# dueSkelMADE.net
KiCad netlist of a schematic drawn in EAGLE
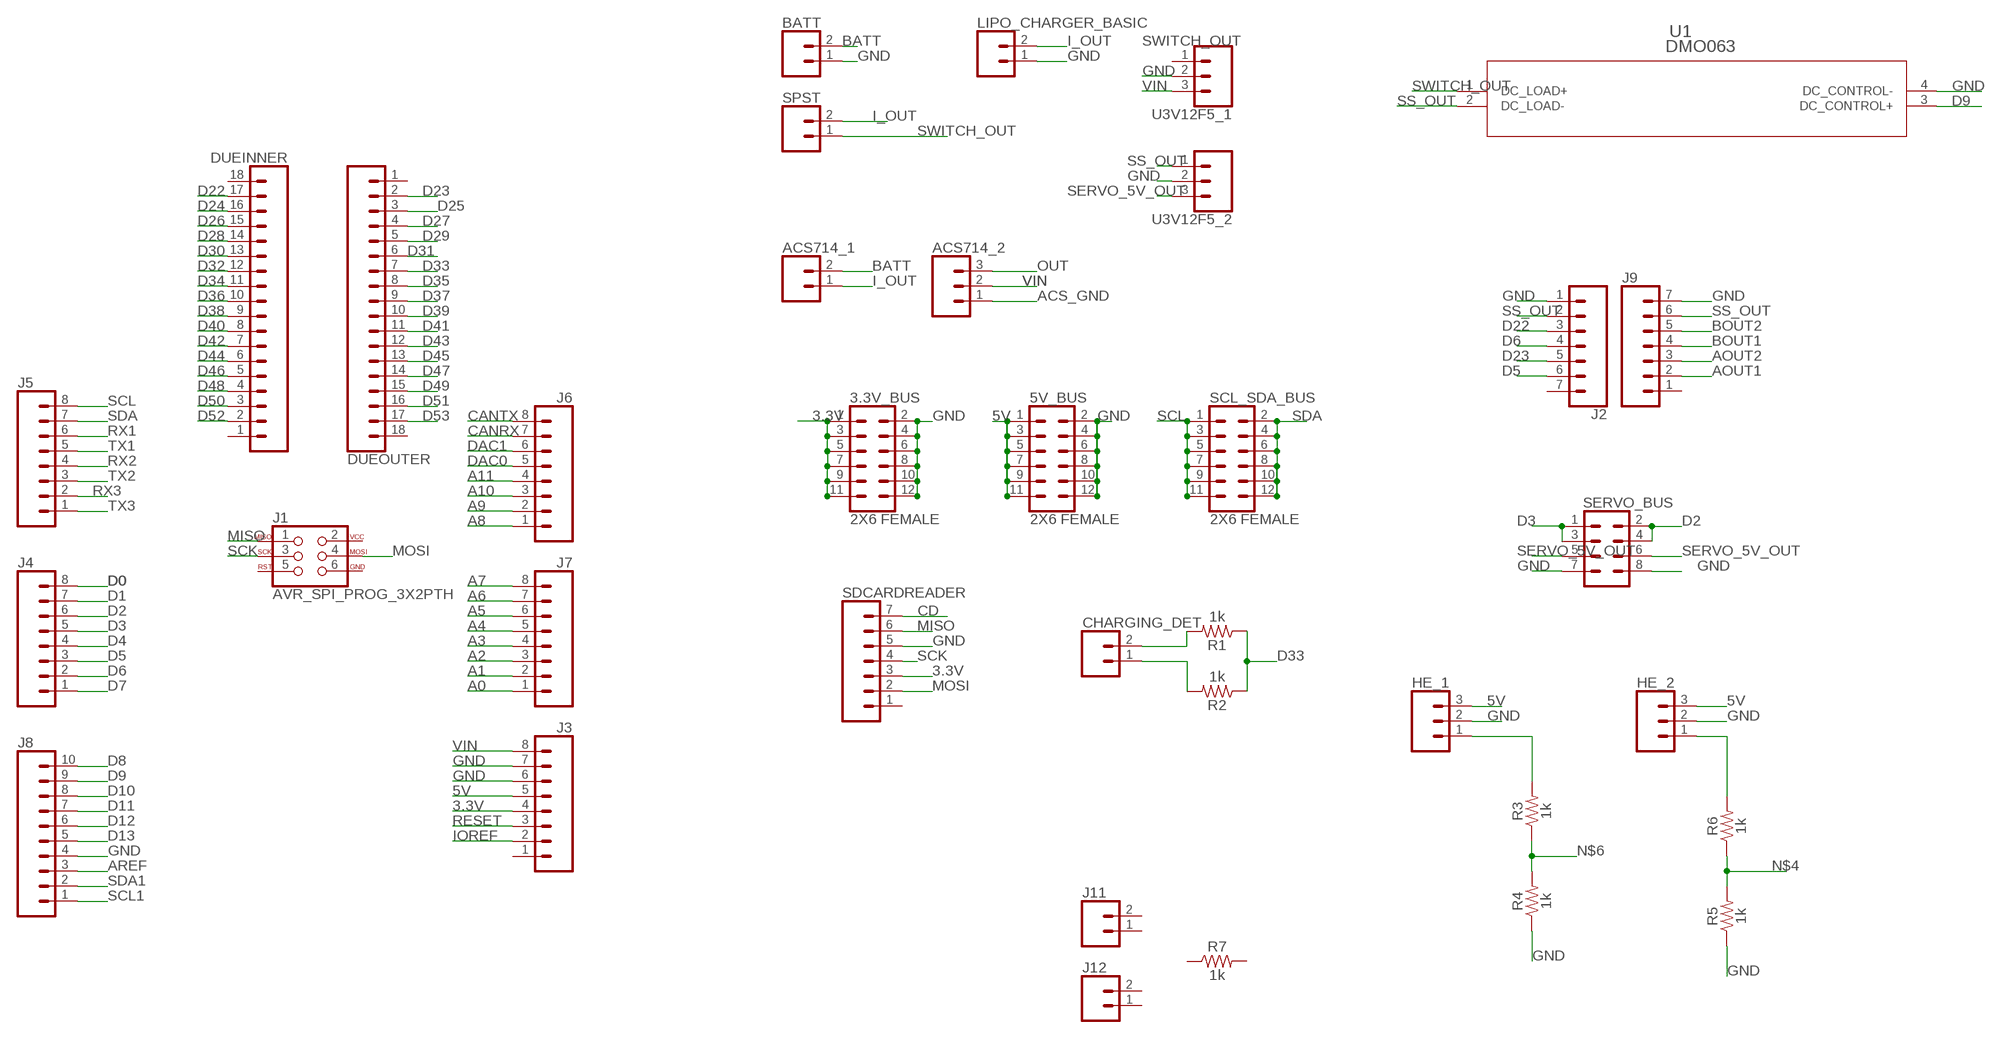
[diagram p0: schematic, sheet 1]

(export (version "E")
  (design (tool "Eeschema 10.0.6"))
  (components
    (comp (ref "3.3V_BUS")
      (value "2X6 FEMALE")
      (footprint "eagle-import:2X6")
      (libsource (lib "eagle-import") (part "CONN_06X2PTH_FEMALE"))
    )
    (comp (ref "5V_BUS")
      (value "2X6 FEMALE")
      (footprint "eagle-import:2X6")
      (libsource (lib "eagle-import") (part "CONN_06X2PTH_FEMALE"))
    )
    (comp (ref "ACS714_1")
      (value "CONN_02")
      (footprint "eagle-import:1X02")
      (libsource (lib "eagle-import") (part "CONN_02"))
    )
    (comp (ref "ACS714_2")
      (value "CONN_03")
      (footprint "eagle-import:1X03")
      (libsource (lib "eagle-import") (part "CONN_03"))
    )
    (comp (ref "BATT")
      (value "CONN_02")
      (footprint "eagle-import:1X02")
      (libsource (lib "eagle-import") (part "CONN_02"))
    )
    (comp (ref "CHARGING_DET")
      (value "CONN_02")
      (footprint "eagle-import:1X02")
      (libsource (lib "eagle-import") (part "CONN_02"))
    )
    (comp (ref "DUEINNER")
      (value "CONN_18")
      (footprint "eagle-import:1X18")
      (libsource (lib "eagle-import") (part "CONN_18"))
    )
    (comp (ref "DUEOUTER")
      (value "CONN_18")
      (footprint "eagle-import:1X18")
      (libsource (lib "eagle-import") (part "CONN_18"))
    )
    (comp (ref "HE_1")
      (value "CONN_03")
      (footprint "eagle-import:1X03")
      (libsource (lib "eagle-import") (part "CONN_03"))
    )
    (comp (ref "HE_2")
      (value "CONN_03")
      (footprint "eagle-import:1X03")
      (libsource (lib "eagle-import") (part "CONN_03"))
    )
    (comp (ref "J1")
      (value "AVR_SPI_PROG_3X2PTH")
      (footprint "eagle-import:2X3")
      (libsource (lib "eagle-import") (part "AVR_SPI_PROG_3X2PTH"))
    )
    (comp (ref "J2")
      (value "CONN_07")
      (footprint "eagle-import:1X07")
      (libsource (lib "eagle-import") (part "CONN_07"))
    )
    (comp (ref "J3")
      (value "CONN_08\"")
      (footprint "eagle-import:1X08")
      (libsource (lib "eagle-import") (part "CONN_08{dblquote}"))
    )
    (comp (ref "J4")
      (value "CONN_08\"")
      (footprint "eagle-import:1X08")
      (libsource (lib "eagle-import") (part "CONN_08{dblquote}"))
    )
    (comp (ref "J5")
      (value "CONN_08\"")
      (footprint "eagle-import:1X08")
      (libsource (lib "eagle-import") (part "CONN_08{dblquote}"))
    )
    (comp (ref "J6")
      (value "CONN_08\"")
      (footprint "eagle-import:1X08")
      (libsource (lib "eagle-import") (part "CONN_08{dblquote}"))
    )
    (comp (ref "J7")
      (value "CONN_08\"")
      (footprint "eagle-import:1X08")
      (libsource (lib "eagle-import") (part "CONN_08{dblquote}"))
    )
    (comp (ref "J8")
      (value "CONN_10\"")
      (footprint "eagle-import:1X10")
      (libsource (lib "eagle-import") (part "CONN_10{dblquote}"))
    )
    (comp (ref "J9")
      (value "CONN_07")
      (footprint "eagle-import:1X07")
      (libsource (lib "eagle-import") (part "CONN_07"))
    )
    (comp (ref "J11")
      (value "CONN_02")
      (footprint "eagle-import:1X02")
      (libsource (lib "eagle-import") (part "CONN_02"))
    )
    (comp (ref "J12")
      (value "CONN_02")
      (footprint "eagle-import:1X02")
      (libsource (lib "eagle-import") (part "CONN_02"))
    )
    (comp (ref "LIPO_CHARGER_BASIC")
      (value "CONN_02")
      (footprint "eagle-import:1X02")
      (libsource (lib "eagle-import") (part "CONN_02"))
    )
    (comp (ref "R1")
      (value "1k")
      (footprint "eagle-import:AXIAL-0.3")
      (libsource (lib "eagle-import") (part "1KOHM-HORIZ-1/4W-1%"))
    )
    (comp (ref "R2")
      (value "1k")
      (footprint "eagle-import:AXIAL-0.3")
      (libsource (lib "eagle-import") (part "1KOHM-HORIZ-1/4W-1%"))
    )
    (comp (ref "R3")
      (value "1k")
      (footprint "eagle-import:AXIAL-0.3")
      (libsource (lib "eagle-import") (part "1KOHM-HORIZ-1/4W-1%"))
    )
    (comp (ref "R4")
      (value "1k")
      (footprint "eagle-import:AXIAL-0.3")
      (libsource (lib "eagle-import") (part "1KOHM-HORIZ-1/4W-1%"))
    )
    (comp (ref "R5")
      (value "1k")
      (footprint "eagle-import:AXIAL-0.3")
      (libsource (lib "eagle-import") (part "1KOHM-HORIZ-1/4W-1%"))
    )
    (comp (ref "R6")
      (value "1k")
      (footprint "eagle-import:AXIAL-0.3")
      (libsource (lib "eagle-import") (part "1KOHM-HORIZ-1/4W-1%"))
    )
    (comp (ref "R7")
      (value "1k")
      (footprint "eagle-import:AXIAL-0.3")
      (libsource (lib "eagle-import") (part "1KOHM-HORIZ-1/4W-1%"))
    )
    (comp (ref "SCL_SDA_BUS")
      (value "2X6 FEMALE")
      (footprint "eagle-import:2X6")
      (libsource (lib "eagle-import") (part "CONN_06X2PTH_FEMALE"))
    )
    (comp (ref "SDCARDREADER")
      (value "CONN_07")
      (footprint "eagle-import:1X07")
      (libsource (lib "eagle-import") (part "CONN_07"))
    )
    (comp (ref "SERVO_BUS")
      (value "CONN_04X2")
      (footprint "eagle-import:2X4")
      (libsource (lib "eagle-import") (part "CONN_04X2"))
    )
    (comp (ref "SPST")
      (value "CONN_02")
      (footprint "eagle-import:1X02")
      (libsource (lib "eagle-import") (part "CONN_02"))
    )
    (comp (ref "U1")
      (value "DMO063")
      (footprint "eagle-import:SIP-4_DMO")
      (libsource (lib "eagle-import") (part "DMO063"))
    )
    (comp (ref "U3V12F5_1")
      (value "CONN_03")
      (footprint "eagle-import:1X03")
      (libsource (lib "eagle-import") (part "CONN_03"))
    )
    (comp (ref "U3V12F5_2")
      (value "CONN_03")
      (footprint "eagle-import:1X03")
      (libsource (lib "eagle-import") (part "CONN_03"))
    )
  )
  (nets
    (net (code "1") (name "/3.3V") (class "Default")
      (node (ref "3.3V_BUS") (pin "1") (pinfunction "1_1") (pintype "passive"))
      (node (ref "3.3V_BUS") (pin "11") (pinfunction "11_11") (pintype "passive"))
      (node (ref "3.3V_BUS") (pin "3") (pinfunction "3_3") (pintype "passive"))
      (node (ref "3.3V_BUS") (pin "5") (pinfunction "5_5") (pintype "passive"))
      (node (ref "3.3V_BUS") (pin "7") (pinfunction "7_7") (pintype "passive"))
      (node (ref "3.3V_BUS") (pin "9") (pinfunction "9_9") (pintype "passive"))
      (node (ref "J3") (pin "4") (pinfunction "4_4") (pintype "passive"))
      (node (ref "SDCARDREADER") (pin "3") (pinfunction "3_3") (pintype "passive"))
    )
    (net (code "2") (name "/5V") (class "Default")
      (node (ref "5V_BUS") (pin "1") (pinfunction "1_1") (pintype "passive"))
      (node (ref "5V_BUS") (pin "11") (pinfunction "11_11") (pintype "passive"))
      (node (ref "5V_BUS") (pin "3") (pinfunction "3_3") (pintype "passive"))
      (node (ref "5V_BUS") (pin "5") (pinfunction "5_5") (pintype "passive"))
      (node (ref "5V_BUS") (pin "7") (pinfunction "7_7") (pintype "passive"))
      (node (ref "5V_BUS") (pin "9") (pinfunction "9_9") (pintype "passive"))
      (node (ref "HE_1") (pin "3") (pinfunction "3_3") (pintype "passive"))
      (node (ref "HE_2") (pin "3") (pinfunction "3_3") (pintype "passive"))
      (node (ref "J3") (pin "5") (pinfunction "5_5") (pintype "passive"))
    )
    (net (code "3") (name "/A0") (class "Default")
      (node (ref "J7") (pin "1") (pinfunction "1_1") (pintype "passive"))
    )
    (net (code "4") (name "/A1") (class "Default")
      (node (ref "J7") (pin "2") (pinfunction "2_2") (pintype "passive"))
    )
    (net (code "5") (name "/A2") (class "Default")
      (node (ref "J7") (pin "3") (pinfunction "3_3") (pintype "passive"))
    )
    (net (code "6") (name "/A3") (class "Default")
      (node (ref "J7") (pin "4") (pinfunction "4_4") (pintype "passive"))
    )
    (net (code "7") (name "/A4") (class "Default")
      (node (ref "J7") (pin "5") (pinfunction "5_5") (pintype "passive"))
    )
    (net (code "8") (name "/A5") (class "Default")
      (node (ref "J7") (pin "6") (pinfunction "6_6") (pintype "passive"))
    )
    (net (code "9") (name "/A6") (class "Default")
      (node (ref "J7") (pin "7") (pinfunction "7_7") (pintype "passive"))
    )
    (net (code "10") (name "/A7") (class "Default")
      (node (ref "J7") (pin "8") (pinfunction "8_8") (pintype "passive"))
    )
    (net (code "11") (name "/A8") (class "Default")
      (node (ref "J6") (pin "1") (pinfunction "1_1") (pintype "passive"))
    )
    (net (code "12") (name "/A9") (class "Default")
      (node (ref "J6") (pin "2") (pinfunction "2_2") (pintype "passive"))
    )
    (net (code "13") (name "/A10") (class "Default")
      (node (ref "J6") (pin "3") (pinfunction "3_3") (pintype "passive"))
    )
    (net (code "14") (name "/A11") (class "Default")
      (node (ref "J6") (pin "4") (pinfunction "4_4") (pintype "passive"))
    )
    (net (code "15") (name "/ACS_GND") (class "Default")
      (node (ref "ACS714_2") (pin "1") (pinfunction "1_1") (pintype "passive"))
    )
    (net (code "16") (name "/AOUT1") (class "Default")
      (node (ref "J9") (pin "2") (pinfunction "2_2") (pintype "passive"))
    )
    (net (code "17") (name "/AOUT2") (class "Default")
      (node (ref "J9") (pin "3") (pinfunction "3_3") (pintype "passive"))
    )
    (net (code "18") (name "/AREF") (class "Default")
      (node (ref "J8") (pin "3") (pinfunction "3_3") (pintype "passive"))
    )
    (net (code "19") (name "/BATT") (class "Default")
      (node (ref "ACS714_1") (pin "2") (pinfunction "2_2") (pintype "passive"))
      (node (ref "BATT") (pin "2") (pinfunction "2_2") (pintype "passive"))
    )
    (net (code "20") (name "/BOUT1") (class "Default")
      (node (ref "J9") (pin "4") (pinfunction "4_4") (pintype "passive"))
    )
    (net (code "21") (name "/BOUT2") (class "Default")
      (node (ref "J9") (pin "5") (pinfunction "5_5") (pintype "passive"))
    )
    (net (code "22") (name "/CANRX") (class "Default")
      (node (ref "J6") (pin "7") (pinfunction "7_7") (pintype "passive"))
    )
    (net (code "23") (name "/CANTX") (class "Default")
      (node (ref "J6") (pin "8") (pinfunction "8_8") (pintype "passive"))
    )
    (net (code "24") (name "/CD") (class "Default")
      (node (ref "SDCARDREADER") (pin "7") (pinfunction "7_7") (pintype "passive"))
    )
    (net (code "25") (name "/D0") (class "Default")
      (node (ref "J4") (pin "8") (pinfunction "8_8") (pintype "passive"))
    )
    (net (code "26") (name "/D1") (class "Default")
      (node (ref "J4") (pin "7") (pinfunction "7_7") (pintype "passive"))
    )
    (net (code "27") (name "/D2") (class "Default")
      (node (ref "J4") (pin "6") (pinfunction "6_6") (pintype "passive"))
      (node (ref "SERVO_BUS") (pin "2") (pinfunction "2_2") (pintype "passive"))
      (node (ref "SERVO_BUS") (pin "4") (pinfunction "4_4") (pintype "passive"))
    )
    (net (code "28") (name "/D3") (class "Default")
      (node (ref "J4") (pin "5") (pinfunction "5_5") (pintype "passive"))
      (node (ref "SERVO_BUS") (pin "1") (pinfunction "1_1") (pintype "passive"))
      (node (ref "SERVO_BUS") (pin "3") (pinfunction "3_3") (pintype "passive"))
    )
    (net (code "29") (name "/D4") (class "Default")
      (node (ref "J4") (pin "4") (pinfunction "4_4") (pintype "passive"))
    )
    (net (code "30") (name "/D5") (class "Default")
      (node (ref "J2") (pin "6") (pinfunction "6_6") (pintype "passive"))
      (node (ref "J4") (pin "3") (pinfunction "3_3") (pintype "passive"))
    )
    (net (code "31") (name "/D6") (class "Default")
      (node (ref "J2") (pin "4") (pinfunction "4_4") (pintype "passive"))
      (node (ref "J4") (pin "2") (pinfunction "2_2") (pintype "passive"))
    )
    (net (code "32") (name "/D7") (class "Default")
      (node (ref "J4") (pin "1") (pinfunction "1_1") (pintype "passive"))
    )
    (net (code "33") (name "/D8") (class "Default")
      (node (ref "J8") (pin "10") (pinfunction "10_10") (pintype "passive"))
    )
    (net (code "34") (name "/D9") (class "Default")
      (node (ref "J8") (pin "9") (pinfunction "9_9") (pintype "passive"))
      (node (ref "U1") (pin "3") (pinfunction "DC_CONTROL+_3") (pintype "passive"))
    )
    (net (code "35") (name "/D10") (class "Default")
      (node (ref "J8") (pin "8") (pinfunction "8_8") (pintype "passive"))
    )
    (net (code "36") (name "/D11") (class "Default")
      (node (ref "J8") (pin "7") (pinfunction "7_7") (pintype "passive"))
    )
    (net (code "37") (name "/D12") (class "Default")
      (node (ref "J8") (pin "6") (pinfunction "6_6") (pintype "passive"))
    )
    (net (code "38") (name "/D13") (class "Default")
      (node (ref "J8") (pin "5") (pinfunction "5_5") (pintype "passive"))
    )
    (net (code "39") (name "/D22") (class "Default")
      (node (ref "DUEINNER") (pin "17") (pinfunction "17_17") (pintype "passive"))
      (node (ref "J2") (pin "3") (pinfunction "3_3") (pintype "passive"))
    )
    (net (code "40") (name "/D23") (class "Default")
      (node (ref "DUEOUTER") (pin "2") (pinfunction "2_2") (pintype "passive"))
      (node (ref "J2") (pin "5") (pinfunction "5_5") (pintype "passive"))
    )
    (net (code "41") (name "/D24") (class "Default")
      (node (ref "DUEINNER") (pin "16") (pinfunction "16_16") (pintype "passive"))
    )
    (net (code "42") (name "/D25") (class "Default")
      (node (ref "DUEOUTER") (pin "3") (pinfunction "3_3") (pintype "passive"))
    )
    (net (code "43") (name "/D26") (class "Default")
      (node (ref "DUEINNER") (pin "15") (pinfunction "15_15") (pintype "passive"))
    )
    (net (code "44") (name "/D27") (class "Default")
      (node (ref "DUEOUTER") (pin "4") (pinfunction "4_4") (pintype "passive"))
    )
    (net (code "45") (name "/D28") (class "Default")
      (node (ref "DUEINNER") (pin "14") (pinfunction "14_14") (pintype "passive"))
    )
    (net (code "46") (name "/D29") (class "Default")
      (node (ref "DUEOUTER") (pin "5") (pinfunction "5_5") (pintype "passive"))
    )
    (net (code "47") (name "/D30") (class "Default")
      (node (ref "DUEINNER") (pin "13") (pinfunction "13_13") (pintype "passive"))
    )
    (net (code "48") (name "/D31") (class "Default")
      (node (ref "DUEOUTER") (pin "6") (pinfunction "6_6") (pintype "passive"))
    )
    (net (code "49") (name "/D32") (class "Default")
      (node (ref "DUEINNER") (pin "12") (pinfunction "12_12") (pintype "passive"))
    )
    (net (code "50") (name "/D33") (class "Default")
      (node (ref "DUEOUTER") (pin "7") (pinfunction "7_7") (pintype "passive"))
      (node (ref "R1") (pin "P$1") (pinfunction "1_P$1") (pintype "passive"))
      (node (ref "R2") (pin "P$1") (pinfunction "1_P$1") (pintype "passive"))
    )
    (net (code "51") (name "/D34") (class "Default")
      (node (ref "DUEINNER") (pin "11") (pinfunction "11_11") (pintype "passive"))
    )
    (net (code "52") (name "/D35") (class "Default")
      (node (ref "DUEOUTER") (pin "8") (pinfunction "8_8") (pintype "passive"))
    )
    (net (code "53") (name "/D36") (class "Default")
      (node (ref "DUEINNER") (pin "10") (pinfunction "10_10") (pintype "passive"))
    )
    (net (code "54") (name "/D37") (class "Default")
      (node (ref "DUEOUTER") (pin "9") (pinfunction "9_9") (pintype "passive"))
    )
    (net (code "55") (name "/D38") (class "Default")
      (node (ref "DUEINNER") (pin "9") (pinfunction "9_9") (pintype "passive"))
    )
    (net (code "56") (name "/D39") (class "Default")
      (node (ref "DUEOUTER") (pin "10") (pinfunction "10_10") (pintype "passive"))
    )
    (net (code "57") (name "/D40") (class "Default")
      (node (ref "DUEINNER") (pin "8") (pinfunction "8_8") (pintype "passive"))
    )
    (net (code "58") (name "/D41") (class "Default")
      (node (ref "DUEOUTER") (pin "11") (pinfunction "11_11") (pintype "passive"))
    )
    (net (code "59") (name "/D42") (class "Default")
      (node (ref "DUEINNER") (pin "7") (pinfunction "7_7") (pintype "passive"))
    )
    (net (code "60") (name "/D43") (class "Default")
      (node (ref "DUEOUTER") (pin "12") (pinfunction "12_12") (pintype "passive"))
    )
    (net (code "61") (name "/D44") (class "Default")
      (node (ref "DUEINNER") (pin "6") (pinfunction "6_6") (pintype "passive"))
    )
    (net (code "62") (name "/D45") (class "Default")
      (node (ref "DUEOUTER") (pin "13") (pinfunction "13_13") (pintype "passive"))
    )
    (net (code "63") (name "/D46") (class "Default")
      (node (ref "DUEINNER") (pin "5") (pinfunction "5_5") (pintype "passive"))
    )
    (net (code "64") (name "/D47") (class "Default")
      (node (ref "DUEOUTER") (pin "14") (pinfunction "14_14") (pintype "passive"))
    )
    (net (code "65") (name "/D48") (class "Default")
      (node (ref "DUEINNER") (pin "4") (pinfunction "4_4") (pintype "passive"))
    )
    (net (code "66") (name "/D49") (class "Default")
      (node (ref "DUEOUTER") (pin "15") (pinfunction "15_15") (pintype "passive"))
    )
    (net (code "67") (name "/D50") (class "Default")
      (node (ref "DUEINNER") (pin "3") (pinfunction "3_3") (pintype "passive"))
    )
    (net (code "68") (name "/D51") (class "Default")
      (node (ref "DUEOUTER") (pin "16") (pinfunction "16_16") (pintype "passive"))
    )
    (net (code "69") (name "/D52") (class "Default")
      (node (ref "DUEINNER") (pin "2") (pinfunction "2_2") (pintype "passive"))
    )
    (net (code "70") (name "/D53") (class "Default")
      (node (ref "DUEOUTER") (pin "17") (pinfunction "17_17") (pintype "passive"))
    )
    (net (code "71") (name "/DAC0") (class "Default")
      (node (ref "J6") (pin "5") (pinfunction "5_5") (pintype "passive"))
    )
    (net (code "72") (name "/DAC1") (class "Default")
      (node (ref "J6") (pin "6") (pinfunction "6_6") (pintype "passive"))
    )
    (net (code "73") (name "/GND") (class "Default")
      (node (ref "3.3V_BUS") (pin "10") (pinfunction "10_10") (pintype "passive"))
      (node (ref "3.3V_BUS") (pin "12") (pinfunction "12_12") (pintype "passive"))
      (node (ref "3.3V_BUS") (pin "2") (pinfunction "2_2") (pintype "passive"))
      (node (ref "3.3V_BUS") (pin "4") (pinfunction "4_4") (pintype "passive"))
      (node (ref "3.3V_BUS") (pin "6") (pinfunction "6_6") (pintype "passive"))
      (node (ref "3.3V_BUS") (pin "8") (pinfunction "8_8") (pintype "passive"))
      (node (ref "5V_BUS") (pin "10") (pinfunction "10_10") (pintype "passive"))
      (node (ref "5V_BUS") (pin "12") (pinfunction "12_12") (pintype "passive"))
      (node (ref "5V_BUS") (pin "2") (pinfunction "2_2") (pintype "passive"))
      (node (ref "5V_BUS") (pin "4") (pinfunction "4_4") (pintype "passive"))
      (node (ref "5V_BUS") (pin "6") (pinfunction "6_6") (pintype "passive"))
      (node (ref "5V_BUS") (pin "8") (pinfunction "8_8") (pintype "passive"))
      (node (ref "BATT") (pin "1") (pinfunction "1_1") (pintype "passive"))
      (node (ref "HE_1") (pin "2") (pinfunction "2_2") (pintype "passive"))
      (node (ref "HE_2") (pin "2") (pinfunction "2_2") (pintype "passive"))
      (node (ref "J2") (pin "1") (pinfunction "1_1") (pintype "passive"))
      (node (ref "J3") (pin "6") (pinfunction "6_6") (pintype "passive"))
      (node (ref "J3") (pin "7") (pinfunction "7_7") (pintype "passive"))
      (node (ref "J8") (pin "4") (pinfunction "4_4") (pintype "passive"))
      (node (ref "J9") (pin "7") (pinfunction "7_7") (pintype "passive"))
      (node (ref "LIPO_CHARGER_BASIC") (pin "1") (pinfunction "1_1") (pintype "passive"))
      (node (ref "R4") (pin "P$1") (pinfunction "1_P$1") (pintype "passive"))
      (node (ref "R5") (pin "P$1") (pinfunction "1_P$1") (pintype "passive"))
      (node (ref "SDCARDREADER") (pin "5") (pinfunction "5_5") (pintype "passive"))
      (node (ref "SERVO_BUS") (pin "7") (pinfunction "7_7") (pintype "passive"))
      (node (ref "SERVO_BUS") (pin "8") (pinfunction "8_8") (pintype "passive"))
      (node (ref "U1") (pin "4") (pinfunction "DC_CONTROL-_4") (pintype "passive"))
      (node (ref "U3V12F5_1") (pin "2") (pinfunction "2_2") (pintype "passive"))
      (node (ref "U3V12F5_2") (pin "2") (pinfunction "2_2") (pintype "passive"))
    )
    (net (code "74") (name "/IOREF") (class "Default")
      (node (ref "J3") (pin "2") (pinfunction "2_2") (pintype "passive"))
    )
    (net (code "75") (name "/I_OUT") (class "Default")
      (node (ref "ACS714_1") (pin "1") (pinfunction "1_1") (pintype "passive"))
      (node (ref "LIPO_CHARGER_BASIC") (pin "2") (pinfunction "2_2") (pintype "passive"))
      (node (ref "SPST") (pin "2") (pinfunction "2_2") (pintype "passive"))
    )
    (net (code "76") (name "/MISO") (class "Default")
      (node (ref "J1") (pin "1") (pinfunction "1_1") (pintype "passive"))
      (node (ref "SDCARDREADER") (pin "6") (pinfunction "6_6") (pintype "passive"))
    )
    (net (code "77") (name "/MOSI") (class "Default")
      (node (ref "J1") (pin "4") (pinfunction "4_4") (pintype "passive"))
      (node (ref "SDCARDREADER") (pin "2") (pinfunction "2_2") (pintype "passive"))
    )
    (net (code "78") (name "/N$4") (class "Default")
      (node (ref "R5") (pin "P$2") (pinfunction "2_P$2") (pintype "passive"))
      (node (ref "R6") (pin "P$1") (pinfunction "1_P$1") (pintype "passive"))
    )
    (net (code "79") (name "/N$6") (class "Default")
      (node (ref "R3") (pin "P$1") (pinfunction "1_P$1") (pintype "passive"))
      (node (ref "R4") (pin "P$2") (pinfunction "2_P$2") (pintype "passive"))
    )
    (net (code "80") (name "/OUT") (class "Default")
      (node (ref "ACS714_2") (pin "3") (pinfunction "3_3") (pintype "passive"))
    )
    (net (code "81") (name "/RESET") (class "Default")
      (node (ref "J3") (pin "3") (pinfunction "3_3") (pintype "passive"))
    )
    (net (code "82") (name "/RX1") (class "Default")
      (node (ref "J5") (pin "6") (pinfunction "6_6") (pintype "passive"))
    )
    (net (code "83") (name "/RX2") (class "Default")
      (node (ref "J5") (pin "4") (pinfunction "4_4") (pintype "passive"))
    )
    (net (code "84") (name "/RX3") (class "Default")
      (node (ref "J5") (pin "2") (pinfunction "2_2") (pintype "passive"))
    )
    (net (code "85") (name "/SCK") (class "Default")
      (node (ref "J1") (pin "3") (pinfunction "3_3") (pintype "passive"))
      (node (ref "SDCARDREADER") (pin "4") (pinfunction "4_4") (pintype "passive"))
    )
    (net (code "86") (name "/SCL") (class "Default")
      (node (ref "J5") (pin "8") (pinfunction "8_8") (pintype "passive"))
      (node (ref "SCL_SDA_BUS") (pin "1") (pinfunction "1_1") (pintype "passive"))
      (node (ref "SCL_SDA_BUS") (pin "11") (pinfunction "11_11") (pintype "passive"))
      (node (ref "SCL_SDA_BUS") (pin "3") (pinfunction "3_3") (pintype "passive"))
      (node (ref "SCL_SDA_BUS") (pin "5") (pinfunction "5_5") (pintype "passive"))
      (node (ref "SCL_SDA_BUS") (pin "7") (pinfunction "7_7") (pintype "passive"))
      (node (ref "SCL_SDA_BUS") (pin "9") (pinfunction "9_9") (pintype "passive"))
    )
    (net (code "87") (name "/SCL1") (class "Default")
      (node (ref "J8") (pin "1") (pinfunction "1_1") (pintype "passive"))
    )
    (net (code "88") (name "/SDA") (class "Default")
      (node (ref "J5") (pin "7") (pinfunction "7_7") (pintype "passive"))
      (node (ref "SCL_SDA_BUS") (pin "10") (pinfunction "10_10") (pintype "passive"))
      (node (ref "SCL_SDA_BUS") (pin "12") (pinfunction "12_12") (pintype "passive"))
      (node (ref "SCL_SDA_BUS") (pin "2") (pinfunction "2_2") (pintype "passive"))
      (node (ref "SCL_SDA_BUS") (pin "4") (pinfunction "4_4") (pintype "passive"))
      (node (ref "SCL_SDA_BUS") (pin "6") (pinfunction "6_6") (pintype "passive"))
      (node (ref "SCL_SDA_BUS") (pin "8") (pinfunction "8_8") (pintype "passive"))
    )
    (net (code "89") (name "/SDA1") (class "Default")
      (node (ref "J8") (pin "2") (pinfunction "2_2") (pintype "passive"))
    )
    (net (code "90") (name "/SERVO_5V_OUT") (class "Default")
      (node (ref "SERVO_BUS") (pin "5") (pinfunction "5_5") (pintype "passive"))
      (node (ref "SERVO_BUS") (pin "6") (pinfunction "6_6") (pintype "passive"))
      (node (ref "U3V12F5_2") (pin "3") (pinfunction "3_3") (pintype "passive"))
    )
    (net (code "91") (name "/SS_OUT") (class "Default")
      (node (ref "J2") (pin "2") (pinfunction "2_2") (pintype "passive"))
      (node (ref "J9") (pin "6") (pinfunction "6_6") (pintype "passive"))
      (node (ref "U1") (pin "2") (pinfunction "DC_LOAD-_2") (pintype "passive"))
      (node (ref "U3V12F5_2") (pin "1") (pinfunction "1_1") (pintype "passive"))
    )
    (net (code "92") (name "/SWITCH_OUT") (class "Default")
      (node (ref "SPST") (pin "1") (pinfunction "1_1") (pintype "passive"))
      (node (ref "U1") (pin "1") (pinfunction "DC_LOAD+_1") (pintype "passive"))
    )
    (net (code "93") (name "/TX1") (class "Default")
      (node (ref "J5") (pin "5") (pinfunction "5_5") (pintype "passive"))
    )
    (net (code "94") (name "/TX2") (class "Default")
      (node (ref "J5") (pin "3") (pinfunction "3_3") (pintype "passive"))
    )
    (net (code "95") (name "/TX3") (class "Default")
      (node (ref "J5") (pin "1") (pinfunction "1_1") (pintype "passive"))
    )
    (net (code "96") (name "/VIN") (class "Default")
      (node (ref "ACS714_2") (pin "2") (pinfunction "2_2") (pintype "passive"))
      (node (ref "J3") (pin "8") (pinfunction "8_8") (pintype "passive"))
      (node (ref "U3V12F5_1") (pin "3") (pinfunction "3_3") (pintype "passive"))
    )
    (net (code "97") (name "Net-(R1-2)") (class "Default")
      (node (ref "CHARGING_DET") (pin "2") (pinfunction "2_2") (pintype "passive"))
      (node (ref "R1") (pin "P$2") (pinfunction "2_P$2") (pintype "passive"))
    )
    (net (code "98") (name "Net-(R2-2)") (class "Default")
      (node (ref "CHARGING_DET") (pin "1") (pinfunction "1_1") (pintype "passive"))
      (node (ref "R2") (pin "P$2") (pinfunction "2_P$2") (pintype "passive"))
    )
    (net (code "99") (name "Net-(R3-2)") (class "Default")
      (node (ref "HE_1") (pin "1") (pinfunction "1_1") (pintype "passive"))
      (node (ref "R3") (pin "P$2") (pinfunction "2_P$2") (pintype "passive"))
    )
    (net (code "100") (name "Net-(R6-2)") (class "Default")
      (node (ref "HE_2") (pin "1") (pinfunction "1_1") (pintype "passive"))
      (node (ref "R6") (pin "P$2") (pinfunction "2_P$2") (pintype "passive"))
    )
    (net (code "101") (name "unconnected-(DUEINNER-Pad1)") (class "Default")
      (node (ref "DUEINNER") (pin "1") (pinfunction "1_1") (pintype "passive"))
    )
    (net (code "102") (name "unconnected-(DUEINNER-Pad18)") (class "Default")
      (node (ref "DUEINNER") (pin "18") (pinfunction "18_18") (pintype "passive"))
    )
    (net (code "103") (name "unconnected-(DUEOUTER-Pad1)") (class "Default")
      (node (ref "DUEOUTER") (pin "1") (pinfunction "1_1") (pintype "passive"))
    )
    (net (code "104") (name "unconnected-(DUEOUTER-Pad18)") (class "Default")
      (node (ref "DUEOUTER") (pin "18") (pinfunction "18_18") (pintype "passive"))
    )
    (net (code "105") (name "unconnected-(J1-Pad2)") (class "Default")
      (node (ref "J1") (pin "2") (pinfunction "2_2") (pintype "passive"))
    )
    (net (code "106") (name "unconnected-(J1-Pad5)") (class "Default")
      (node (ref "J1") (pin "5") (pinfunction "5_5") (pintype "passive"))
    )
    (net (code "107") (name "unconnected-(J1-Pad6)") (class "Default")
      (node (ref "J1") (pin "6") (pinfunction "6_6") (pintype "passive"))
    )
    (net (code "108") (name "unconnected-(J2-Pad7)") (class "Default")
      (node (ref "J2") (pin "7") (pinfunction "7_7") (pintype "passive"))
    )
    (net (code "109") (name "unconnected-(J3-Pad1)") (class "Default")
      (node (ref "J3") (pin "1") (pinfunction "1_1") (pintype "passive"))
    )
    (net (code "110") (name "unconnected-(J9-Pad1)") (class "Default")
      (node (ref "J9") (pin "1") (pinfunction "1_1") (pintype "passive"))
    )
    (net (code "111") (name "unconnected-(J11-Pad1)") (class "Default")
      (node (ref "J11") (pin "1") (pinfunction "1_1") (pintype "passive"))
    )
    (net (code "112") (name "unconnected-(J11-Pad2)") (class "Default")
      (node (ref "J11") (pin "2") (pinfunction "2_2") (pintype "passive"))
    )
    (net (code "113") (name "unconnected-(J12-Pad1)") (class "Default")
      (node (ref "J12") (pin "1") (pinfunction "1_1") (pintype "passive"))
    )
    (net (code "114") (name "unconnected-(J12-Pad2)") (class "Default")
      (node (ref "J12") (pin "2") (pinfunction "2_2") (pintype "passive"))
    )
    (net (code "115") (name "unconnected-(R7-1-PadP$1)") (class "Default")
      (node (ref "R7") (pin "P$1") (pinfunction "1_P$1") (pintype "passive"))
    )
    (net (code "116") (name "unconnected-(R7-2-PadP$2)") (class "Default")
      (node (ref "R7") (pin "P$2") (pinfunction "2_P$2") (pintype "passive"))
    )
    (net (code "117") (name "unconnected-(SDCARDREADER-Pad1)") (class "Default")
      (node (ref "SDCARDREADER") (pin "1") (pinfunction "1_1") (pintype "passive"))
    )
    (net (code "118") (name "unconnected-(U3V12F5_1-Pad1)") (class "Default")
      (node (ref "U3V12F5_1") (pin "1") (pinfunction "1_1") (pintype "passive"))
    )
  )
)
